# Grove_-_RJ45_Adapter_v1_0b.net
KiCad netlist of a schematic drawn in EAGLE
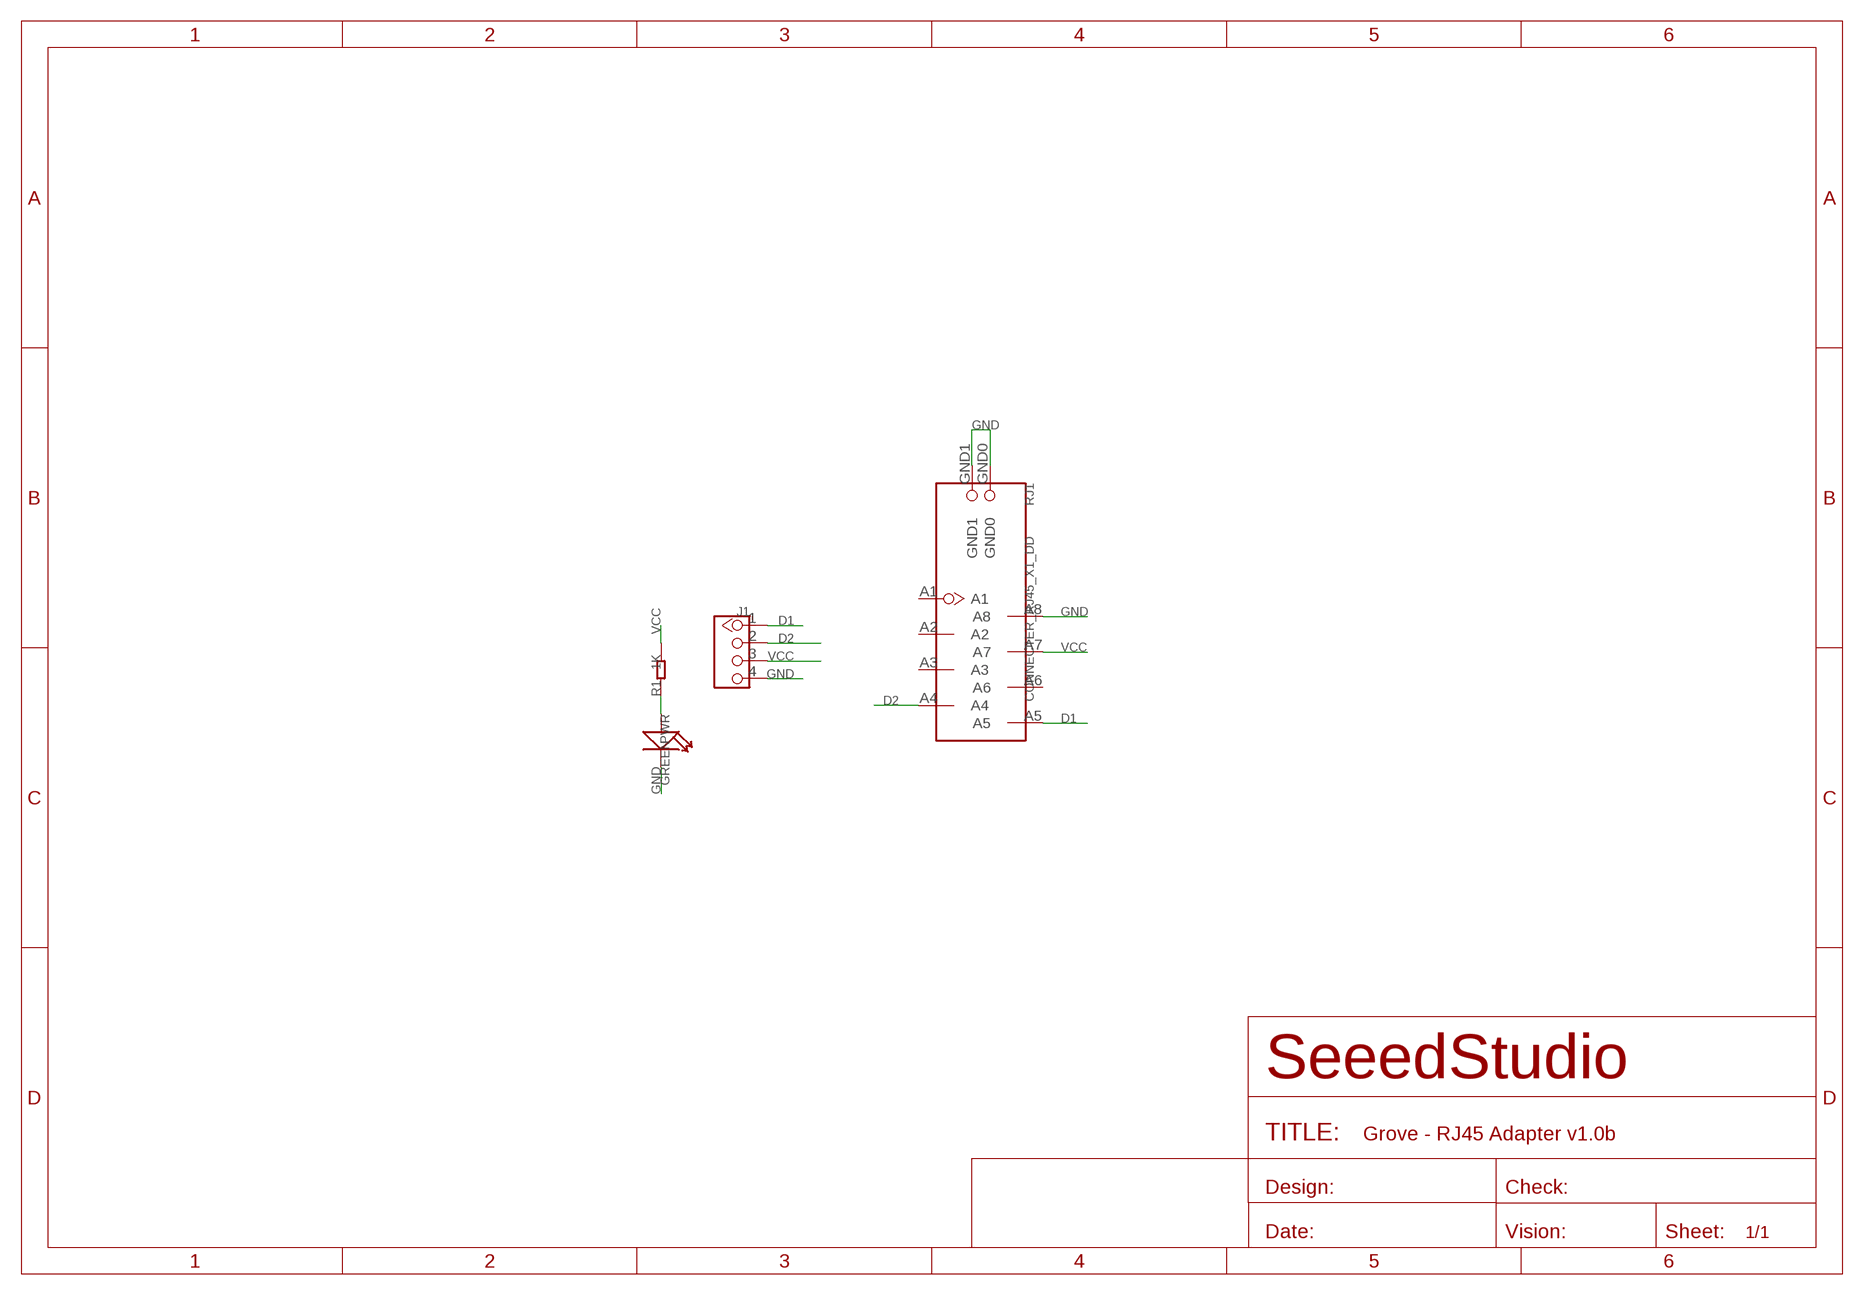
[diagram p0: schematic, sheet 1]

(export (version "E")
  (design (tool "Eeschema 10.0.6"))
  (components
    (comp (ref "J1")
      (value "TWIG-4P-2.0-2.0")
      (footprint "eagle-import:4P-2.0")
      (libsource (lib "eagle-import") (part "TWIG-4P-2.0-2.0"))
    )
    (comp (ref "PWR")
      (value "GREEN")
      (footprint "eagle-import:LED-0603")
      (libsource (lib "eagle-import") (part "LED'0603'"))
    )
    (comp (ref "R1")
      (value "1K")
      (footprint "eagle-import:R0603")
      (libsource (lib "eagle-import") (part "R-0603"))
    )
    (comp (ref "RJ1")
      (value "CONNECTER_RJ45_X1_DD")
      (footprint "eagle-import:CONNECTER_RJ45_X1")
      (libsource (lib "eagle-import") (part "CONNECTER_RJ45_X1_DD"))
    )
  )
  (nets
    (net (code "1") (name "/D1") (class "Default")
      (node (ref "J1") (pin "1") (pinfunction "1_1") (pintype "bidirectional"))
      (node (ref "RJ1") (pin "A5") (pinfunction "A5_A5") (pintype "bidirectional"))
    )
    (net (code "2") (name "/D2") (class "Default")
      (node (ref "J1") (pin "2") (pinfunction "2_2") (pintype "bidirectional"))
      (node (ref "RJ1") (pin "A4") (pinfunction "A4_A4") (pintype "bidirectional"))
    )
    (net (code "3") (name "/GND") (class "Default")
      (node (ref "J1") (pin "4") (pinfunction "4_4") (pintype "bidirectional"))
      (node (ref "PWR") (pin "-") (pinfunction "-_-") (pintype "passive"))
      (node (ref "RJ1") (pin "A8") (pinfunction "A8_A8") (pintype "bidirectional"))
      (node (ref "RJ1") (pin "GND0") (pinfunction "GND0_GND0") (pintype "bidirectional"))
      (node (ref "RJ1") (pin "GND1") (pinfunction "GND1_GND1") (pintype "bidirectional"))
    )
    (net (code "4") (name "/VCC") (class "Default")
      (node (ref "J1") (pin "3") (pinfunction "3_3") (pintype "bidirectional"))
      (node (ref "R1") (pin "2") (pinfunction "2_2") (pintype "passive"))
      (node (ref "RJ1") (pin "A7") (pinfunction "A7_A7") (pintype "bidirectional"))
    )
    (net (code "5") (name "Net-(PWR-Pad+)") (class "Default")
      (node (ref "PWR") (pin "+") (pinfunction "+_+") (pintype "passive"))
      (node (ref "R1") (pin "1") (pinfunction "1_1") (pintype "passive"))
    )
    (net (code "6") (name "unconnected-(RJ1-PadA1)") (class "Default")
      (node (ref "RJ1") (pin "A1") (pinfunction "A1_A1") (pintype "bidirectional"))
    )
    (net (code "7") (name "unconnected-(RJ1-PadA2)") (class "Default")
      (node (ref "RJ1") (pin "A2") (pinfunction "A2_A2") (pintype "bidirectional"))
    )
    (net (code "8") (name "unconnected-(RJ1-PadA3)") (class "Default")
      (node (ref "RJ1") (pin "A3") (pinfunction "A3_A3") (pintype "bidirectional"))
    )
    (net (code "9") (name "unconnected-(RJ1-PadA6)") (class "Default")
      (node (ref "RJ1") (pin "A6") (pinfunction "A6_A6") (pintype "bidirectional"))
    )
  )
)
